# 7_-_ADC_Chip.net
KiCad netlist of a schematic drawn in Altium Designer
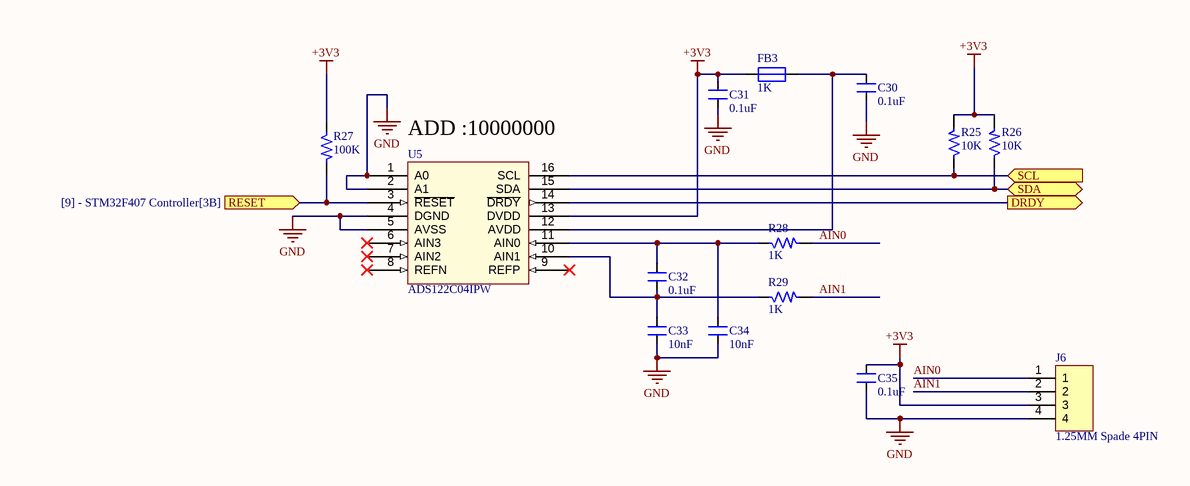
[diagram p0: [7] - ADC Chip.SchDoc]

(export (version "E")
  (design (tool "Eeschema 10.0.6"))
  (components
    (comp (ref "C30")
      (value "0.1uF")
      (footprint "CAP_0805")
      (description "0.1µF ±10% 50V Ceramic Capacitor X7R 0805 (2012 Metric)")
      (fields
        (field (name "MANUFACTURER") "Samsung")
        (field (name "MANUFACTURER PART NUMBER") "CL21B104KBCNNNC")
      )
      (libsource (lib "ESTEEMPCBLIB") (part "CAP_0.1uF-50V-10%-0805"))
    )
    (comp (ref "C31")
      (value "0.1uF")
      (footprint "CAP_0805")
      (description "0.1µF ±10% 50V Ceramic Capacitor X7R 0805 (2012 Metric)")
      (fields
        (field (name "MANUFACTURER") "Samsung")
        (field (name "MANUFACTURER PART NUMBER") "CL21B104KBCNNNC")
      )
      (libsource (lib "ESTEEMPCBLIB") (part "CAP_0.1uF-50V-10%-0805"))
    )
    (comp (ref "C32")
      (value "0.1uF")
      (footprint "CAP_0805")
      (description "0.1µF ±10% 50V Ceramic Capacitor X7R 0805 (2012 Metric)")
      (fields
        (field (name "MANUFACTURER") "Samsung")
        (field (name "MANUFACTURER PART NUMBER") "CL21B104KBCNNNC")
      )
      (libsource (lib "ESTEEMPCBLIB") (part "CAP_0.1uF-50V-10%-0805"))
    )
    (comp (ref "C33")
      (value "10nF")
      (footprint "CAP_0805")
      (description "10000pF ±10% 50V Ceramic Capacitor X7R 0805 (2012 Metric)")
      (fields
        (field (name "MANUFACTURER") "Samsung")
        (field (name "MANUFACTURER PART NUMBER") "C0805C103K5RECAUTO")
      )
      (libsource (lib "ESTEEMPCBLIB") (part "CAP_10nF-50V-10%-0805"))
    )
    (comp (ref "C34")
      (value "10nF")
      (footprint "CAP_0805")
      (description "10000pF ±10% 50V Ceramic Capacitor X7R 0805 (2012 Metric)")
      (fields
        (field (name "MANUFACTURER") "Samsung")
        (field (name "MANUFACTURER PART NUMBER") "C0805C103K5RECAUTO")
      )
      (libsource (lib "ESTEEMPCBLIB") (part "CAP_10nF-50V-10%-0805"))
    )
    (comp (ref "C35")
      (value "0.1uF")
      (footprint "CAP_0805")
      (description "0.1µF ±10% 50V Ceramic Capacitor X7R 0805 (2012 Metric)")
      (fields
        (field (name "MANUFACTURER") "Samsung")
        (field (name "MANUFACTURER PART NUMBER") "CL21B104KBCNNNC")
      )
      (libsource (lib "ESTEEMPCBLIB") (part "CAP_0.1uF-50V-10%-0805"))
    )
    (comp (ref "FB3")
      (value "1K")
      (footprint "IND_0805")
      (description "1 kOhms @ 100MHz 1 Power Line Ferrite Bead 0805 (2012 Metric) 1.6A")
      (fields
        (field (name "MANUFACTURER") "Laird")
        (field (name "MANUFACTURER PART NUMBER") "BLM21SP102SH1D")
      )
      (libsource (lib "ESTEEMPCBLIB") (part "FB_1K-100MHZ-1.6A-0805"))
    )
    (comp (ref "J6")
      (value "1.25MM Spade 4PIN")
      (footprint "CON4_50_653004117322_TH_RA")
      (description "4 Pins, 1 Row 1.25mm Pitch, right angle Connector, male")
      (fields (field (name "MANUFACTURER PART NUMBER") "653004117322") (field (name "MANUFACTURER") "JST"))
      (libsource (lib "ESTEEMPCBLIB") (part "CON-PLG_4X1-50-RA-TH"))
    )
    (comp (ref "R25")
      (value "10K")
      (footprint "RES_0603")
      (description "10 kOhms ±1% 0.1W, 1/10W Chip Resistor 0603 (1608 Metric) Automotive AEC-Q200 Thick Film")
      (fields (field (name "MANUFACTURER") "Walsin") (field (name "MANUFACTURER PART NUMBER") "WR06X1002FTL"))
      (libsource (lib "ESTEEMPCBLIB") (part "RES_10K-0.1W-1%-0603"))
    )
    (comp (ref "R26")
      (value "10K")
      (footprint "RES_0603")
      (description "10 kOhms ±1% 0.1W, 1/10W Chip Resistor 0603 (1608 Metric) Automotive AEC-Q200 Thick Film")
      (fields (field (name "MANUFACTURER") "Walsin") (field (name "MANUFACTURER PART NUMBER") "WR06X1002FTL"))
      (libsource (lib "ESTEEMPCBLIB") (part "RES_10K-0.1W-1%-0603"))
    )
    (comp (ref "R27")
      (value "100K")
      (footprint "RES_0603")
      (description "100 kOhms ±1% 0.1W, 1/10W Chip Resistor 0603 (1608 Metric) Automotive AEC-Q200 Thick Film")
      (fields
        (field (name "MANUFACTURER") "Stackpole Electronics")
        (field (name "MANUFACTURER PART NUMBER") "RMCF0603FT100K")
      )
      (libsource (lib "ESTEEMPCBLIB") (part "RES_100K-0.1W-1%-0603"))
    )
    (comp (ref "R28")
      (value "1K")
      (footprint "RES_0603")
      (description "1 kOhms ±1% 0.1W, 1/10W Chip Resistor 0603 (1608 Metric) Automotive AEC-Q200 Thick Film")
      (fields (field (name "MANUFACTURER") "Walsin") (field (name "MANUFACTURER PART NUMBER") "WR06X1001FTL"))
      (libsource (lib "ESTEEMPCBLIB") (part "RES_1K-0.1W-1%-0603"))
    )
    (comp (ref "R29")
      (value "1K")
      (footprint "RES_0603")
      (description "1 kOhms ±1% 0.1W, 1/10W Chip Resistor 0603 (1608 Metric) Automotive AEC-Q200 Thick Film")
      (fields (field (name "MANUFACTURER") "Walsin") (field (name "MANUFACTURER PART NUMBER") "WR06X1001FTL"))
      (libsource (lib "ESTEEMPCBLIB") (part "RES_1K-0.1W-1%-0603"))
    )
    (comp (ref "U5")
      (value "ADS122C04IPW")
      (footprint "TSSOP16_25-59_294_54X14_SMT")
      (description "24 Bit Analog to Digital Converter 4 Input 1 Sigma-Delta 16-TSSOP")
      (fields (field (name "MANUFACTURER") "Texas Instruments"))
      (libsource (lib "ESTEEMPCBLIB") (part "IC_ADS122C04IPW"))
    )
  )
  (nets
    (net (code "1") (name "+3V3") (class "Default")
      (node (ref "C31") (pin "2") (pinfunction "2_2") (pintype "passive"))
      (node (ref "C35") (pin "2") (pinfunction "2_2") (pintype "passive"))
      (node (ref "FB3") (pin "1") (pinfunction "1_1") (pintype "passive"))
      (node (ref "J6") (pin "3") (pinfunction "3_3") (pintype "passive"))
      (node (ref "R25") (pin "2") (pinfunction "2_2") (pintype "passive"))
      (node (ref "R26") (pin "2") (pinfunction "2_2") (pintype "passive"))
      (node (ref "R27") (pin "1") (pinfunction "1_1") (pintype "passive"))
      (node (ref "U5") (pin "13") (pinfunction "DVDD_13") (pintype "power_in"))
    )
    (net (code "2") (name "/AIN0") (class "Default")
      (node (ref "J6") (pin "1") (pinfunction "1_1") (pintype "passive"))
      (node (ref "R28") (pin "2") (pinfunction "2_2") (pintype "passive"))
    )
    (net (code "3") (name "/AIN1") (class "Default")
      (node (ref "J6") (pin "2") (pinfunction "2_2") (pintype "passive"))
      (node (ref "R29") (pin "2") (pinfunction "2_2") (pintype "passive"))
    )
    (net (code "4") (name "/DRDY") (class "Default")
      (node (ref "U5") (pin "14") (pinfunction "DRDY_14") (pintype "output"))
    )
    (net (code "5") (name "/RESET") (class "Default")
      (node (ref "R27") (pin "2") (pinfunction "2_2") (pintype "passive"))
      (node (ref "U5") (pin "3") (pinfunction "RESET_3") (pintype "input"))
    )
    (net (code "6") (name "/SCL") (class "Default")
      (node (ref "R25") (pin "1") (pinfunction "1_1") (pintype "passive"))
      (node (ref "U5") (pin "16") (pinfunction "SCL_16") (pintype "open_collector"))
    )
    (net (code "7") (name "/SDA") (class "Default")
      (node (ref "R26") (pin "1") (pinfunction "1_1") (pintype "passive"))
      (node (ref "U5") (pin "15") (pinfunction "SDA_15") (pintype "open_collector"))
    )
    (net (code "8") (name "GND") (class "Default")
      (node (ref "C30") (pin "1") (pinfunction "1_1") (pintype "passive"))
      (node (ref "C31") (pin "1") (pinfunction "1_1") (pintype "passive"))
      (node (ref "C33") (pin "1") (pinfunction "1_1") (pintype "passive"))
      (node (ref "C34") (pin "1") (pinfunction "1_1") (pintype "passive"))
      (node (ref "C35") (pin "1") (pinfunction "1_1") (pintype "passive"))
      (node (ref "J6") (pin "4") (pinfunction "4_4") (pintype "passive"))
      (node (ref "U5") (pin "1") (pinfunction "A0_1") (pintype "passive"))
      (node (ref "U5") (pin "2") (pinfunction "A1_2") (pintype "passive"))
      (node (ref "U5") (pin "4") (pinfunction "DGND_4") (pintype "power_in"))
      (node (ref "U5") (pin "5") (pinfunction "AVSS_5") (pintype "power_in"))
    )
    (net (code "9") (name "Net-(U5-AIN0)") (class "Default")
      (node (ref "C32") (pin "2") (pinfunction "2_2") (pintype "passive"))
      (node (ref "C34") (pin "2") (pinfunction "2_2") (pintype "passive"))
      (node (ref "R28") (pin "1") (pinfunction "1_1") (pintype "passive"))
      (node (ref "U5") (pin "11") (pinfunction "AIN0_11") (pintype "input"))
    )
    (net (code "10") (name "Net-(U5-AIN1)") (class "Default")
      (node (ref "C32") (pin "1") (pinfunction "1_1") (pintype "passive"))
      (node (ref "C33") (pin "2") (pinfunction "2_2") (pintype "passive"))
      (node (ref "R29") (pin "1") (pinfunction "1_1") (pintype "passive"))
      (node (ref "U5") (pin "10") (pinfunction "AIN1_10") (pintype "input"))
    )
    (net (code "11") (name "Net-(U5-AVDD)") (class "Default")
      (node (ref "C30") (pin "2") (pinfunction "2_2") (pintype "passive"))
      (node (ref "FB3") (pin "2") (pinfunction "2_2") (pintype "passive"))
      (node (ref "U5") (pin "12") (pinfunction "AVDD_12") (pintype "power_in"))
    )
    (net (code "12") (name "unconnected-(U5-AIN2-Pad7)") (class "Default")
      (node (ref "U5") (pin "7") (pinfunction "AIN2_7") (pintype "input+no_connect"))
    )
    (net (code "13") (name "unconnected-(U5-AIN3-Pad6)") (class "Default")
      (node (ref "U5") (pin "6") (pinfunction "AIN3_6") (pintype "input+no_connect"))
    )
    (net (code "14") (name "unconnected-(U5-REFN-Pad8)") (class "Default")
      (node (ref "U5") (pin "8") (pinfunction "REFN_8") (pintype "input+no_connect"))
    )
    (net (code "15") (name "unconnected-(U5-REFP-Pad9)") (class "Default")
      (node (ref "U5") (pin "9") (pinfunction "REFP_9") (pintype "input+no_connect"))
    )
  )
)
